# Sheet1.net
KiCad netlist of a schematic drawn in Altium Designer
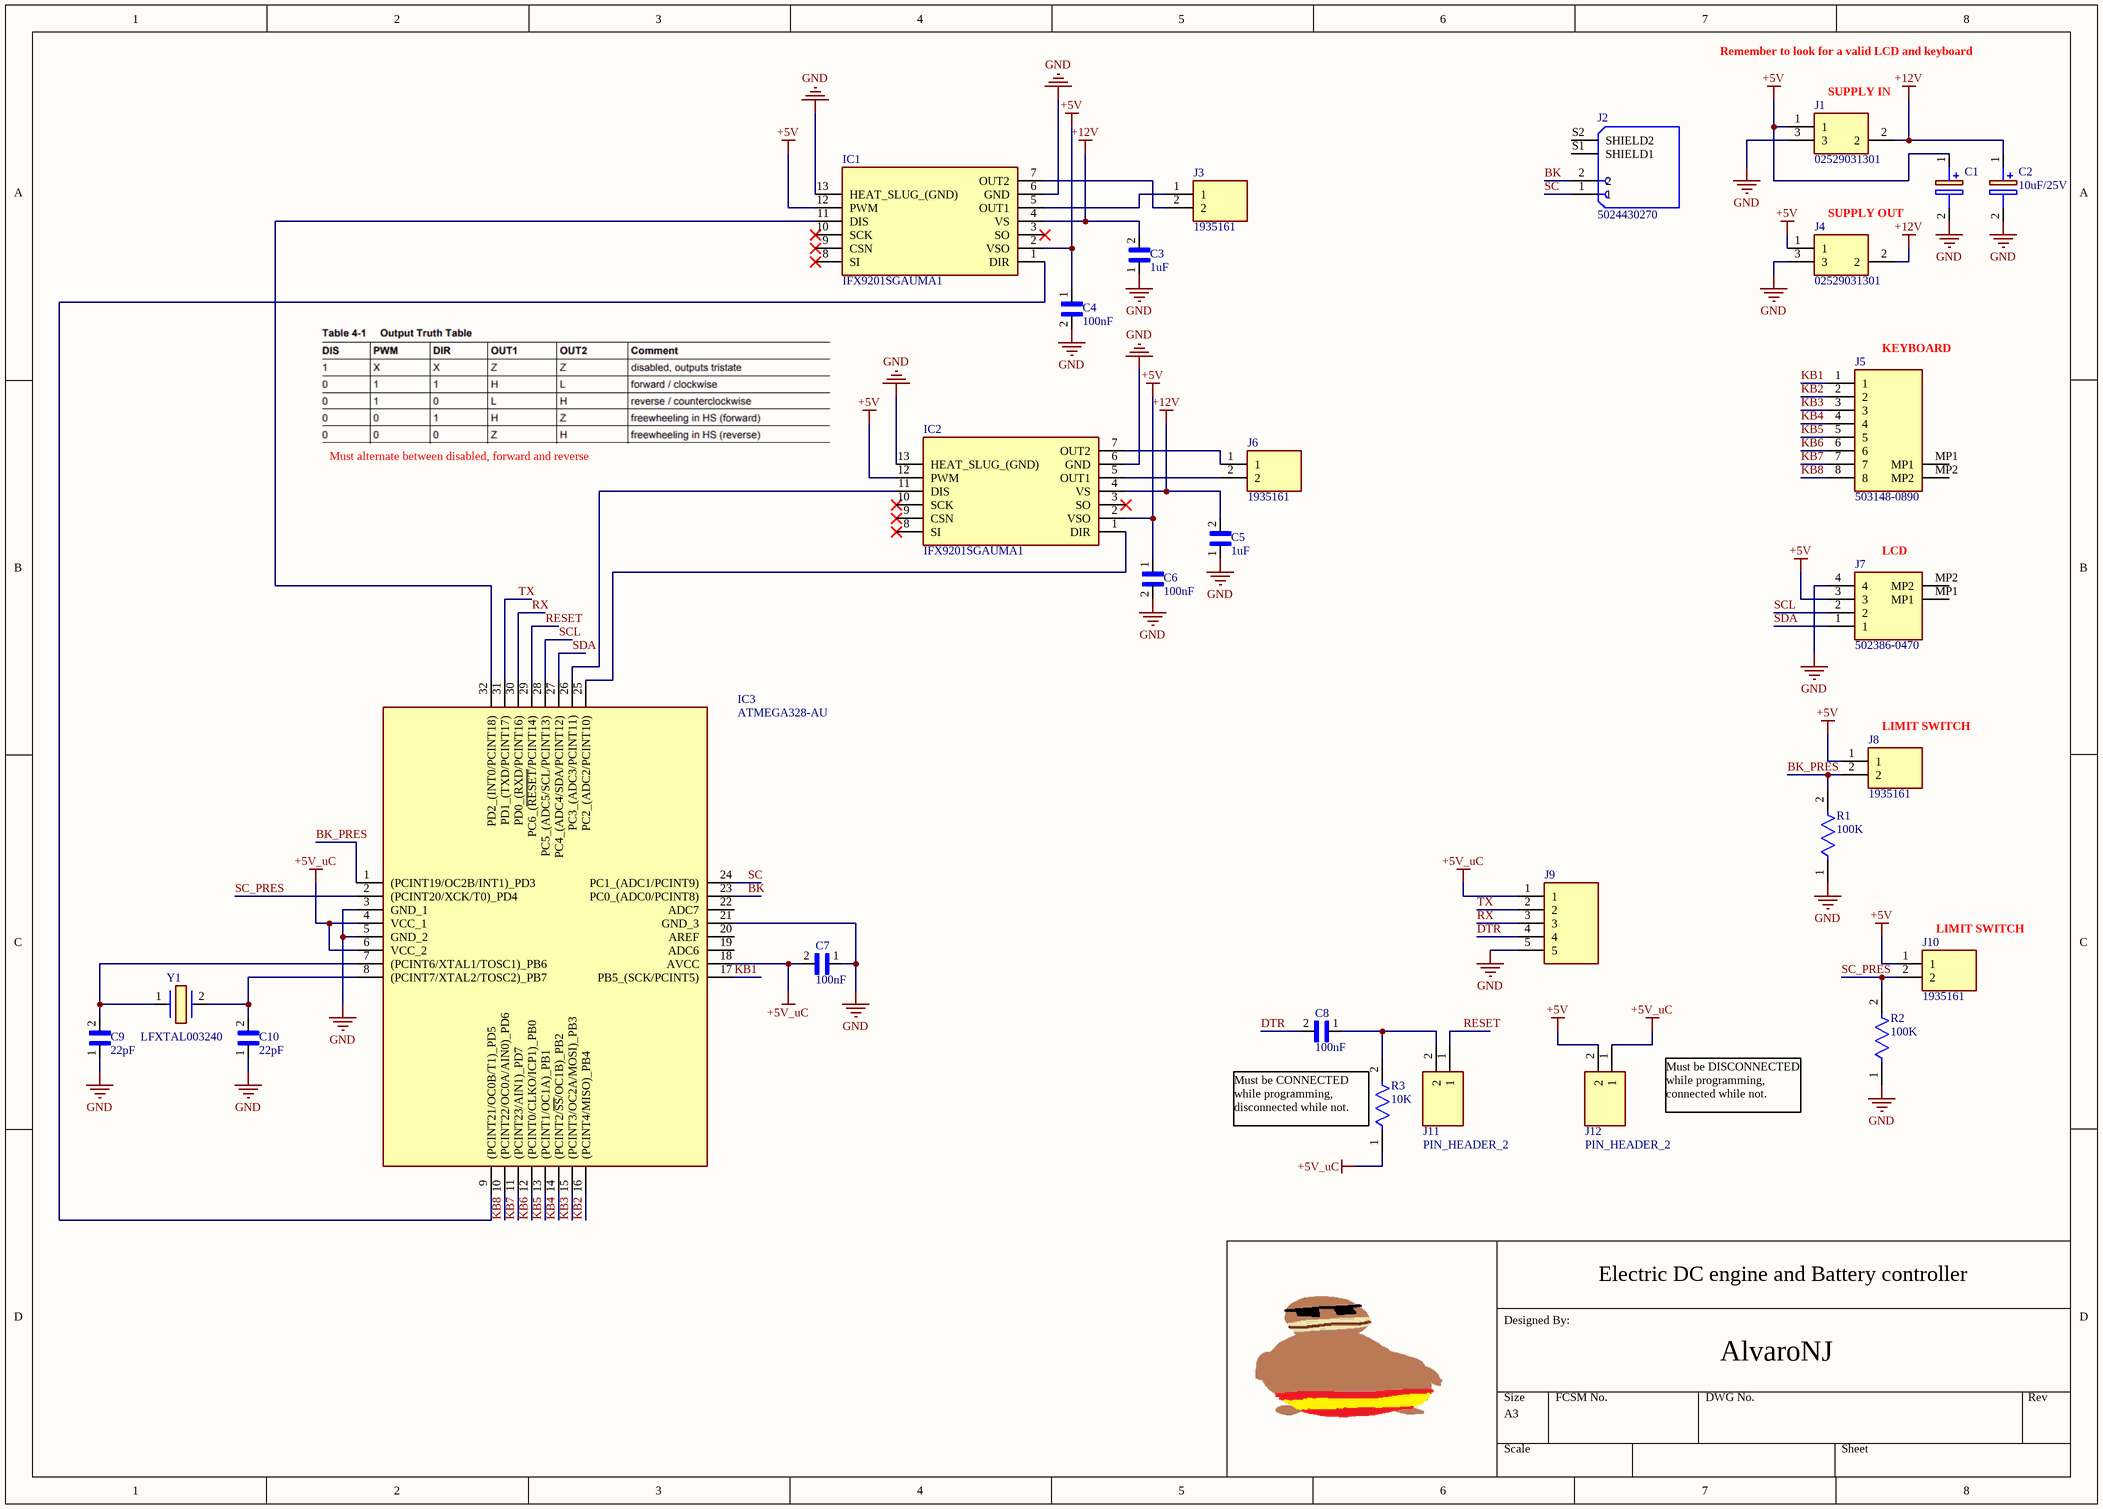
[diagram p0: Sheet1.SchDoc]

(export (version "E")
  (design (tool "Eeschema 10.0.6"))
  (components
    (comp (ref "C1")
      (value "EEE-1CA100SR")
      (footprint "PcbLib1:EEE1AA220WR")
      (description "Capacitor Polarised")
      (fields (field (name "MOUSER PART NUMBER") "667-EEE-1CA100SR"))
      (libsource (lib "*") (part "EEE-1CA100SR"))
    )
    (comp (ref "C2")
      (value "10uF/25V")
      (footprint "PcbLib1:CAPPRD200W52D500H1250")
      (description "Capacitor Polarised")
      (fields
        (field (name "MANUFACTURER") "Wurth Elektronik")
        (field (name "MANUFACTURER PART NUMBER") "860010472002")
      )
      (libsource (lib "*") (part "860010472002"))
    )
    (comp (ref "C3")
      (value "1uF")
      (footprint "0603C")
      (description "Cap Ceramic 1uF 25V")
      (fields
        (field (name "MANUFACTURER") "Samsung")
        (field (name "MANUFACTURER PART NUMBER") "CL10A105KA8NNNC")
      )
      (libsource (lib "Schlib1") (part "Ceramic_Capacitor"))
    )
    (comp (ref "C4")
      (value "100nF")
      (footprint "0603C")
      (description "Cap Ceramic 100nF")
      (fields
        (field (name "MANUFACTURER") "Kyocera")
        (field (name "MANUFACTURER PART NUMBER") "KGM15BR71E104KT")
      )
      (libsource (lib "") (part "Ceramic_Capacitor_2"))
    )
    (comp (ref "C5")
      (value "1uF")
      (footprint "0603C")
      (description "Cap Ceramic 1uF 25V")
      (fields
        (field (name "MANUFACTURER") "Samsung")
        (field (name "MANUFACTURER PART NUMBER") "CL10A105KA8NNNC")
      )
      (libsource (lib "Schlib1") (part "Ceramic_Capacitor"))
    )
    (comp (ref "C6")
      (value "100nF")
      (footprint "0603C")
      (description "Cap Ceramic 100nF")
      (fields
        (field (name "MANUFACTURER") "Kyocera")
        (field (name "MANUFACTURER PART NUMBER") "KGM15BR71E104KT")
      )
      (libsource (lib "") (part "Ceramic_Capacitor_2"))
    )
    (comp (ref "C7")
      (value "100nF")
      (footprint "0603C")
      (description "Cap Ceramic 22pF")
      (fields
        (field (name "MANUFACTURER") "Kyocera")
        (field (name "MANUFACTURER PART NUMBER") "KGM15BR71E104KT")
      )
      (libsource (lib "") (part "Ceramic_Capacitor_1"))
    )
    (comp (ref "C8")
      (value "100nF")
      (footprint "0603C")
      (description "Cap Ceramic 22pF")
      (fields
        (field (name "MANUFACTURER") "Kyocera")
        (field (name "MANUFACTURER PART NUMBER") "KGM15BR71E104KT")
      )
      (libsource (lib "") (part "Ceramic_Capacitor_1"))
    )
    (comp (ref "C9")
      (value "22pF")
      (footprint "0603C")
      (description "Cap Ceramic 22pF")
      (fields
        (field (name "MANUFACTURER") "Kyocera")
        (field (name "MANUFACTURER PART NUMBER") "KGM15ACG1C220KT")
      )
      (libsource (lib "Schlib1") (part "Ceramic_Capacitor"))
    )
    (comp (ref "C10")
      (value "22pF")
      (footprint "0603C")
      (description "Cap Ceramic 22pF")
      (fields
        (field (name "MANUFACTURER") "Kyocera")
        (field (name "MANUFACTURER PART NUMBER") "KGM15ACG1C220KT")
      )
      (libsource (lib "Schlib1") (part "Ceramic_Capacitor"))
    )
    (comp (ref "IC1")
      (value "IFX9201SGAUMA1")
      (footprint "PcbLib1:PG-DSO-12-17")
      (description "Integrated Circuit")
      (fields (field (name "MOUSER PART NUMBER") "726-IFX9201SGAUMA1"))
      (libsource (lib "Schlib1") (part "IFX9201SGAUMA1"))
    )
    (comp (ref "IC2")
      (value "IFX9201SGAUMA1")
      (footprint "PcbLib1:PG-DSO-12-17")
      (description "Integrated Circuit")
      (fields (field (name "MOUSER PART NUMBER") "726-IFX9201SGAUMA1"))
      (libsource (lib "Schlib1") (part "IFX9201SGAUMA1"))
    )
    (comp (ref "IC3")
      (value "ATMEGA328-AU")
      (footprint "QFP80P900X900X120-32N")
      (description "Integrated Circuit")
      (fields (field (name "MOUSER PART NUMBER") "556-ATMEGA328-AU"))
      (libsource (lib "Schlib1") (part "ATMEGA328-AU"))
    )
    (comp (ref "J1")
      (value "02529031301")
      (footprint "PcbLib1:02529031301")
      (description "Connector")
      (fields (field (name "MOUSER PART NUMBER") "617-02529031301"))
      (libsource (lib "Schlib1") (part "02529031301"))
    )
    (comp (ref "J2")
      (value "5024430270")
      (footprint "MOLEX_5024430270")
      (libsource (lib "Schlib1") (part "5024430270"))
    )
    (comp (ref "J3")
      (value "1935161")
      (footprint "PcbLib1:1935161")
      (description "Connector")
      (fields (field (name "MOUSER PART NUMBER") "651-1935161"))
      (libsource (lib "*") (part "1935161"))
    )
    (comp (ref "J4")
      (value "02529031301")
      (footprint "PcbLib1:02529031301")
      (description "Connector")
      (fields (field (name "MOUSER PART NUMBER") "617-02529031301"))
      (libsource (lib "Schlib1") (part "02529031301"))
    )
    (comp (ref "J5")
      (value "503148-0890")
      (footprint "PcbLib1:5031480890")
      (description "Connector")
      (fields (field (name "MOUSER PART NUMBER") "538-503148-0890"))
      (libsource (lib "*") (part "503148-0890"))
    )
    (comp (ref "J6")
      (value "1935161")
      (footprint "PcbLib1:1935161")
      (description "Connector")
      (fields (field (name "MOUSER PART NUMBER") "651-1935161"))
      (libsource (lib "*") (part "1935161"))
    )
    (comp (ref "J7")
      (value "502386-0470")
      (footprint "PcbLib1:5023860470")
      (description "Connector")
      (fields (field (name "MOUSER PART NUMBER") "538-502386-0470"))
      (libsource (lib "*") (part "502386-0470"))
    )
    (comp (ref "J8")
      (value "1935161")
      (footprint "PcbLib1:1935161")
      (description "Connector")
      (fields (field (name "MOUSER PART NUMBER") "651-1935161"))
      (libsource (lib "*") (part "1935161"))
    )
    (comp (ref "J9")
      (value "MOLEX,_C-GRID_III,_90120,_8_WAY,_1_ROW,_STRAIGHT_PIN_HEADER")
      (footprint "HDRV8W65P0X254_1X8_2010X249X945P - duplicate")
      (description "Connector")
      (fields (field (name "MANUFACTURER_PART_NUMBER") "MOLEX"))
      (libsource (lib "Schlib1") (part "MOLEX,_C-GRID_III,_90120,_8_WAY,_1_ROW,_STRAIGHT_PIN_HEADER"))
    )
    (comp (ref "J10")
      (value "1935161")
      (footprint "PcbLib1:1935161")
      (description "Connector")
      (fields (field (name "MOUSER PART NUMBER") "651-1935161"))
      (libsource (lib "*") (part "1935161"))
    )
    (comp (ref "J11")
      (value "PIN_HEADER_2")
      (footprint "PINHEADER2")
      (description "Connector")
      (fields (field (name "MANUFACTURER_PART_NUMBER") "MOLEX"))
      (libsource (lib "Schlib1") (part "PIN_HEADER_2"))
    )
    (comp (ref "J12")
      (value "PIN_HEADER_2")
      (footprint "PINHEADER2")
      (description "Connector")
      (fields (field (name "MANUFACTURER_PART_NUMBER") "MOLEX"))
      (libsource (lib "Schlib1") (part "PIN_HEADER_2"))
    )
    (comp (ref "R1")
      (value "100K")
      (footprint "0603R")
      (fields
        (field (name "MANUFACTURER") "Yageo")
        (field (name "MANUFACTURER PART NUMBER") "RC0603FR-10100KL")
      )
      (libsource (lib "Schlib1") (part "Resistor"))
    )
    (comp (ref "R2")
      (value "100K")
      (footprint "0603R")
      (fields
        (field (name "MANUFACTURER") "Yageo")
        (field (name "MANUFACTURER PART NUMBER") "RC0603FR-10100KL")
      )
      (libsource (lib "Schlib1") (part "Resistor"))
    )
    (comp (ref "R3")
      (value "10K")
      (footprint "0603R")
      (fields
        (field (name "MANUFACTURER") "Yageo")
        (field (name "MANUFACTURER PART NUMBER") "RC0603FR-1010KL")
      )
      (libsource (lib "Schlib1") (part "Resistor"))
    )
    (comp (ref "Y1")
      (value "LFXTAL003240")
      (footprint "IQD-HC-49-4H")
      (description "Crystal or Oscillator")
      (libsource (lib "Schlib1") (part "LFXTAL003240"))
    )
  )
  (nets
    (net (code "1") (name "+5V") (class "Default")
      (node (ref "C1") (pin "1") (pinfunction "+_1") (pintype "passive"))
      (node (ref "C4") (pin "1") (pinfunction "1_1") (pintype "passive"))
      (node (ref "C6") (pin "1") (pinfunction "1_1") (pintype "passive"))
      (node (ref "IC1") (pin "12") (pinfunction "PWM_12") (pintype "passive"))
      (node (ref "IC1") (pin "2") (pinfunction "VSO_2") (pintype "passive"))
      (node (ref "IC2") (pin "12") (pinfunction "PWM_12") (pintype "passive"))
      (node (ref "IC2") (pin "2") (pinfunction "VSO_2") (pintype "passive"))
      (node (ref "J1") (pin "1") (pinfunction "1_1") (pintype "passive"))
      (node (ref "J10") (pin "1") (pinfunction "1_1") (pintype "passive"))
      (node (ref "J12") (pin "2") (pinfunction "2_2") (pintype "passive"))
      (node (ref "J4") (pin "1") (pinfunction "1_1") (pintype "passive"))
      (node (ref "J7") (pin "3") (pinfunction "3_3") (pintype "passive"))
      (node (ref "J8") (pin "1") (pinfunction "1_1") (pintype "passive"))
    )
    (net (code "2") (name "+5V_uC") (class "Default")
      (node (ref "C7") (pin "2") (pinfunction "2_2") (pintype "passive"))
      (node (ref "IC3") (pin "18") (pinfunction "AVCC_18") (pintype "passive"))
      (node (ref "IC3") (pin "4") (pinfunction "VCC_1_4") (pintype "passive"))
      (node (ref "IC3") (pin "6") (pinfunction "VCC_2_6") (pintype "passive"))
      (node (ref "J12") (pin "1") (pinfunction "1_1") (pintype "passive"))
      (node (ref "J9") (pin "1") (pinfunction "1_1") (pintype "passive"))
      (node (ref "R3") (pin "1") (pinfunction "1_1") (pintype "passive"))
    )
    (net (code "3") (name "+12V") (class "Default")
      (node (ref "C2") (pin "1") (pinfunction "+_1") (pintype "passive"))
      (node (ref "C3") (pin "2") (pinfunction "2_2") (pintype "passive"))
      (node (ref "C5") (pin "2") (pinfunction "2_2") (pintype "passive"))
      (node (ref "IC1") (pin "4") (pinfunction "VS_4") (pintype "passive"))
      (node (ref "IC2") (pin "4") (pinfunction "VS_4") (pintype "passive"))
      (node (ref "J1") (pin "2") (pinfunction "2_2") (pintype "passive"))
      (node (ref "J4") (pin "2") (pinfunction "2_2") (pintype "passive"))
    )
    (net (code "4") (name "/BK") (class "Default")
      (node (ref "IC3") (pin "23") (pinfunction "PC0_(ADC0/PCINT8)_23") (pintype "passive"))
      (node (ref "J2") (pin "2") (pinfunction "2_2") (pintype "passive"))
    )
    (net (code "5") (name "/BK_PRES") (class "Default")
      (node (ref "IC3") (pin "1") (pinfunction "(PCINT19/OC2B/INT1)_PD3_1") (pintype "passive"))
      (node (ref "J8") (pin "2") (pinfunction "2_2") (pintype "passive"))
      (node (ref "R1") (pin "2") (pinfunction "2_2") (pintype "passive"))
    )
    (net (code "6") (name "/DTR") (class "Default")
      (node (ref "C8") (pin "2") (pinfunction "2_2") (pintype "passive"))
      (node (ref "J9") (pin "4") (pinfunction "4_4") (pintype "passive"))
    )
    (net (code "7") (name "/KB1") (class "Default")
      (node (ref "IC3") (pin "17") (pinfunction "PB5_(SCK/PCINT5)_17") (pintype "passive"))
      (node (ref "J5") (pin "1") (pinfunction "1_1") (pintype "passive"))
    )
    (net (code "8") (name "/KB2") (class "Default")
      (node (ref "IC3") (pin "16") (pinfunction "(PCINT4/MISO)_PB4_16") (pintype "passive"))
      (node (ref "J5") (pin "2") (pinfunction "2_2") (pintype "passive"))
    )
    (net (code "9") (name "/KB3") (class "Default")
      (node (ref "IC3") (pin "15") (pinfunction "(PCINT3/OC2A/MOSI)_PB3_15") (pintype "passive"))
      (node (ref "J5") (pin "3") (pinfunction "3_3") (pintype "passive"))
    )
    (net (code "10") (name "/KB4") (class "Default")
      (node (ref "IC3") (pin "14") (pinfunction "(PCINT2/~{SS}/OC1B)_PB2_14") (pintype "passive"))
      (node (ref "J5") (pin "4") (pinfunction "4_4") (pintype "passive"))
    )
    (net (code "11") (name "/KB5") (class "Default")
      (node (ref "IC3") (pin "13") (pinfunction "(PCINT1/OC1A)_PB1_13") (pintype "passive"))
      (node (ref "J5") (pin "5") (pinfunction "5_5") (pintype "passive"))
    )
    (net (code "12") (name "/KB6") (class "Default")
      (node (ref "IC3") (pin "12") (pinfunction "(PCINT0/CLKO/ICP1)_PB0_12") (pintype "passive"))
      (node (ref "J5") (pin "6") (pinfunction "6_6") (pintype "passive"))
    )
    (net (code "13") (name "/KB7") (class "Default")
      (node (ref "IC3") (pin "11") (pinfunction "(PCINT23/AIN1)_PD7_11") (pintype "passive"))
      (node (ref "J5") (pin "7") (pinfunction "7_7") (pintype "passive"))
    )
    (net (code "14") (name "/KB8") (class "Default")
      (node (ref "IC3") (pin "10") (pinfunction "(PCINT22/OC0A/AIN0)_PD6_10") (pintype "passive"))
      (node (ref "J5") (pin "8") (pinfunction "8_8") (pintype "passive"))
    )
    (net (code "15") (name "/RESET") (class "Default")
      (node (ref "IC3") (pin "29") (pinfunction "PC6_(~{RESET}/PCINT14)_29") (pintype "passive"))
      (node (ref "J11") (pin "1") (pinfunction "1_1") (pintype "passive"))
    )
    (net (code "16") (name "/RX") (class "Default")
      (node (ref "IC3") (pin "30") (pinfunction "PD0_(RXD/PCINT16)_30") (pintype "passive"))
      (node (ref "J9") (pin "3") (pinfunction "3_3") (pintype "passive"))
    )
    (net (code "17") (name "/SC") (class "Default")
      (node (ref "IC3") (pin "24") (pinfunction "PC1_(ADC1/PCINT9)_24") (pintype "passive"))
      (node (ref "J2") (pin "1") (pinfunction "1_1") (pintype "passive"))
    )
    (net (code "18") (name "/SCL") (class "Default")
      (node (ref "IC3") (pin "28") (pinfunction "PC5_(ADC5/SCL/PCINT13)_28") (pintype "passive"))
      (node (ref "J7") (pin "2") (pinfunction "2_2") (pintype "passive"))
    )
    (net (code "19") (name "/SC_PRES") (class "Default")
      (node (ref "IC3") (pin "2") (pinfunction "(PCINT20/XCK/T0)_PD4_2") (pintype "passive"))
      (node (ref "J10") (pin "2") (pinfunction "2_2") (pintype "passive"))
      (node (ref "R2") (pin "2") (pinfunction "2_2") (pintype "passive"))
    )
    (net (code "20") (name "/SDA") (class "Default")
      (node (ref "IC3") (pin "27") (pinfunction "PC4_(ADC4/SDA/PCINT12)_27") (pintype "passive"))
      (node (ref "J7") (pin "1") (pinfunction "1_1") (pintype "passive"))
    )
    (net (code "21") (name "/TX") (class "Default")
      (node (ref "IC3") (pin "31") (pinfunction "PD1_(TXD/PCINT17)_31") (pintype "passive"))
      (node (ref "J9") (pin "2") (pinfunction "2_2") (pintype "passive"))
    )
    (net (code "22") (name "GND") (class "Default")
      (node (ref "C1") (pin "2") (pinfunction "-_2") (pintype "passive"))
      (node (ref "C10") (pin "1") (pinfunction "1_1") (pintype "passive"))
      (node (ref "C2") (pin "2") (pinfunction "-_2") (pintype "passive"))
      (node (ref "C3") (pin "1") (pinfunction "1_1") (pintype "passive"))
      (node (ref "C4") (pin "2") (pinfunction "2_2") (pintype "passive"))
      (node (ref "C5") (pin "1") (pinfunction "1_1") (pintype "passive"))
      (node (ref "C6") (pin "2") (pinfunction "2_2") (pintype "passive"))
      (node (ref "C7") (pin "1") (pinfunction "1_1") (pintype "passive"))
      (node (ref "C9") (pin "1") (pinfunction "1_1") (pintype "passive"))
      (node (ref "IC1") (pin "13") (pinfunction "HEAT_SLUG_(GND)_13") (pintype "passive"))
      (node (ref "IC1") (pin "6") (pinfunction "GND_6") (pintype "passive"))
      (node (ref "IC2") (pin "13") (pinfunction "HEAT_SLUG_(GND)_13") (pintype "passive"))
      (node (ref "IC2") (pin "6") (pinfunction "GND_6") (pintype "passive"))
      (node (ref "IC3") (pin "21") (pinfunction "GND_3_21") (pintype "passive"))
      (node (ref "IC3") (pin "3") (pinfunction "GND_1_3") (pintype "passive"))
      (node (ref "IC3") (pin "5") (pinfunction "GND_2_5") (pintype "passive"))
      (node (ref "J1") (pin "3") (pinfunction "3_3") (pintype "passive"))
      (node (ref "J4") (pin "3") (pinfunction "3_3") (pintype "passive"))
      (node (ref "J7") (pin "4") (pinfunction "4_4") (pintype "passive"))
      (node (ref "J9") (pin "5") (pinfunction "5_5") (pintype "passive"))
      (node (ref "R1") (pin "1") (pinfunction "1_1") (pintype "passive"))
      (node (ref "R2") (pin "1") (pinfunction "1_1") (pintype "passive"))
    )
    (net (code "23") (name "Net-(C8-Pad1)") (class "Default")
      (node (ref "C8") (pin "1") (pinfunction "1_1") (pintype "passive"))
      (node (ref "J11") (pin "2") (pinfunction "2_2") (pintype "passive"))
      (node (ref "R3") (pin "2") (pinfunction "2_2") (pintype "passive"))
    )
    (net (code "24") (name "Net-(IC1-DIR)") (class "Default")
      (node (ref "IC1") (pin "1") (pinfunction "DIR_1") (pintype "passive"))
      (node (ref "IC3") (pin "9") (pinfunction "(PCINT21/OC0B/T1)_PD5_9") (pintype "passive"))
    )
    (net (code "25") (name "Net-(IC1-DIS)") (class "Default")
      (node (ref "IC1") (pin "11") (pinfunction "DIS_11") (pintype "passive"))
      (node (ref "IC3") (pin "32") (pinfunction "PD2_(INT0/PCINT18)_32") (pintype "passive"))
    )
    (net (code "26") (name "Net-(IC1-OUT1)") (class "Default")
      (node (ref "IC1") (pin "5") (pinfunction "OUT1_5") (pintype "passive"))
      (node (ref "J3") (pin "1") (pinfunction "1_1") (pintype "passive"))
    )
    (net (code "27") (name "Net-(IC1-OUT2)") (class "Default")
      (node (ref "IC1") (pin "7") (pinfunction "OUT2_7") (pintype "passive"))
      (node (ref "J3") (pin "2") (pinfunction "2_2") (pintype "passive"))
    )
    (net (code "28") (name "Net-(IC2-DIR)") (class "Default")
      (node (ref "IC2") (pin "1") (pinfunction "DIR_1") (pintype "passive"))
      (node (ref "IC3") (pin "25") (pinfunction "PC2_(ADC2/PCINT10)_25") (pintype "passive"))
    )
    (net (code "29") (name "Net-(IC2-DIS)") (class "Default")
      (node (ref "IC2") (pin "11") (pinfunction "DIS_11") (pintype "passive"))
      (node (ref "IC3") (pin "26") (pinfunction "PC3_(ADC3/PCINT11)_26") (pintype "passive"))
    )
    (net (code "30") (name "Net-(IC2-OUT1)") (class "Default")
      (node (ref "IC2") (pin "5") (pinfunction "OUT1_5") (pintype "passive"))
      (node (ref "J6") (pin "2") (pinfunction "2_2") (pintype "passive"))
    )
    (net (code "31") (name "Net-(IC2-OUT2)") (class "Default")
      (node (ref "IC2") (pin "7") (pinfunction "OUT2_7") (pintype "passive"))
      (node (ref "J6") (pin "1") (pinfunction "1_1") (pintype "passive"))
    )
    (net (code "32") (name "Net-(IC3-(PCINT6{slash}XTAL1{slash}TOSC1)_PB6)") (class "Default")
      (node (ref "C9") (pin "2") (pinfunction "2_2") (pintype "passive"))
      (node (ref "IC3") (pin "7") (pinfunction "(PCINT6/XTAL1/TOSC1)_PB6_7") (pintype "passive"))
      (node (ref "Y1") (pin "1") (pinfunction "1_1") (pintype "passive"))
    )
    (net (code "33") (name "Net-(IC3-(PCINT7{slash}XTAL2{slash}TOSC2)_PB7)") (class "Default")
      (node (ref "C10") (pin "2") (pinfunction "2_2") (pintype "passive"))
      (node (ref "IC3") (pin "8") (pinfunction "(PCINT7/XTAL2/TOSC2)_PB7_8") (pintype "passive"))
      (node (ref "Y1") (pin "2") (pinfunction "2_2") (pintype "passive"))
    )
    (net (code "34") (name "unconnected-(IC1-CSN-Pad9)") (class "Default")
      (node (ref "IC1") (pin "9") (pinfunction "CSN_9") (pintype "passive+no_connect"))
    )
    (net (code "35") (name "unconnected-(IC1-SCK-Pad10)") (class "Default")
      (node (ref "IC1") (pin "10") (pinfunction "SCK_10") (pintype "passive+no_connect"))
    )
    (net (code "36") (name "unconnected-(IC1-SI-Pad8)") (class "Default")
      (node (ref "IC1") (pin "8") (pinfunction "SI_8") (pintype "passive+no_connect"))
    )
    (net (code "37") (name "unconnected-(IC1-SO-Pad3)") (class "Default")
      (node (ref "IC1") (pin "3") (pinfunction "SO_3") (pintype "passive+no_connect"))
    )
    (net (code "38") (name "unconnected-(IC2-CSN-Pad9)") (class "Default")
      (node (ref "IC2") (pin "9") (pinfunction "CSN_9") (pintype "passive+no_connect"))
    )
    (net (code "39") (name "unconnected-(IC2-SCK-Pad10)") (class "Default")
      (node (ref "IC2") (pin "10") (pinfunction "SCK_10") (pintype "passive+no_connect"))
    )
    (net (code "40") (name "unconnected-(IC2-SI-Pad8)") (class "Default")
      (node (ref "IC2") (pin "8") (pinfunction "SI_8") (pintype "passive+no_connect"))
    )
    (net (code "41") (name "unconnected-(IC2-SO-Pad3)") (class "Default")
      (node (ref "IC2") (pin "3") (pinfunction "SO_3") (pintype "passive+no_connect"))
    )
    (net (code "42") (name "unconnected-(IC3-ADC6-Pad19)") (class "Default")
      (node (ref "IC3") (pin "19") (pinfunction "ADC6_19") (pintype "passive"))
    )
    (net (code "43") (name "unconnected-(IC3-ADC7-Pad22)") (class "Default")
      (node (ref "IC3") (pin "22") (pinfunction "ADC7_22") (pintype "passive"))
    )
    (net (code "44") (name "unconnected-(IC3-AREF-Pad20)") (class "Default")
      (node (ref "IC3") (pin "20") (pinfunction "AREF_20") (pintype "passive"))
    )
    (net (code "45") (name "unconnected-(J2-SHIELD1-PadS1)") (class "Default")
      (node (ref "J2") (pin "S1") (pinfunction "SHIELD1_S1") (pintype "passive"))
    )
    (net (code "46") (name "unconnected-(J2-SHIELD2-PadS2)") (class "Default")
      (node (ref "J2") (pin "S2") (pinfunction "SHIELD2_S2") (pintype "passive"))
    )
    (net (code "47") (name "unconnected-(J5-PadMP1)") (class "Default")
      (node (ref "J5") (pin "MP1") (pinfunction "MP1_MP1") (pintype "passive"))
    )
    (net (code "48") (name "unconnected-(J5-PadMP2)") (class "Default")
      (node (ref "J5") (pin "MP2") (pinfunction "MP2_MP2") (pintype "passive"))
    )
    (net (code "49") (name "unconnected-(J7-PadMP1)") (class "Default")
      (node (ref "J7") (pin "MP1") (pinfunction "MP1_MP1") (pintype "passive"))
    )
    (net (code "50") (name "unconnected-(J7-PadMP2)") (class "Default")
      (node (ref "J7") (pin "MP2") (pinfunction "MP2_MP2") (pintype "passive"))
    )
  )
)
